# SCH_Wiring-harness-For-Activa_2025-07-03.net
KiCad netlist of a schematic drawn in EasyEDA
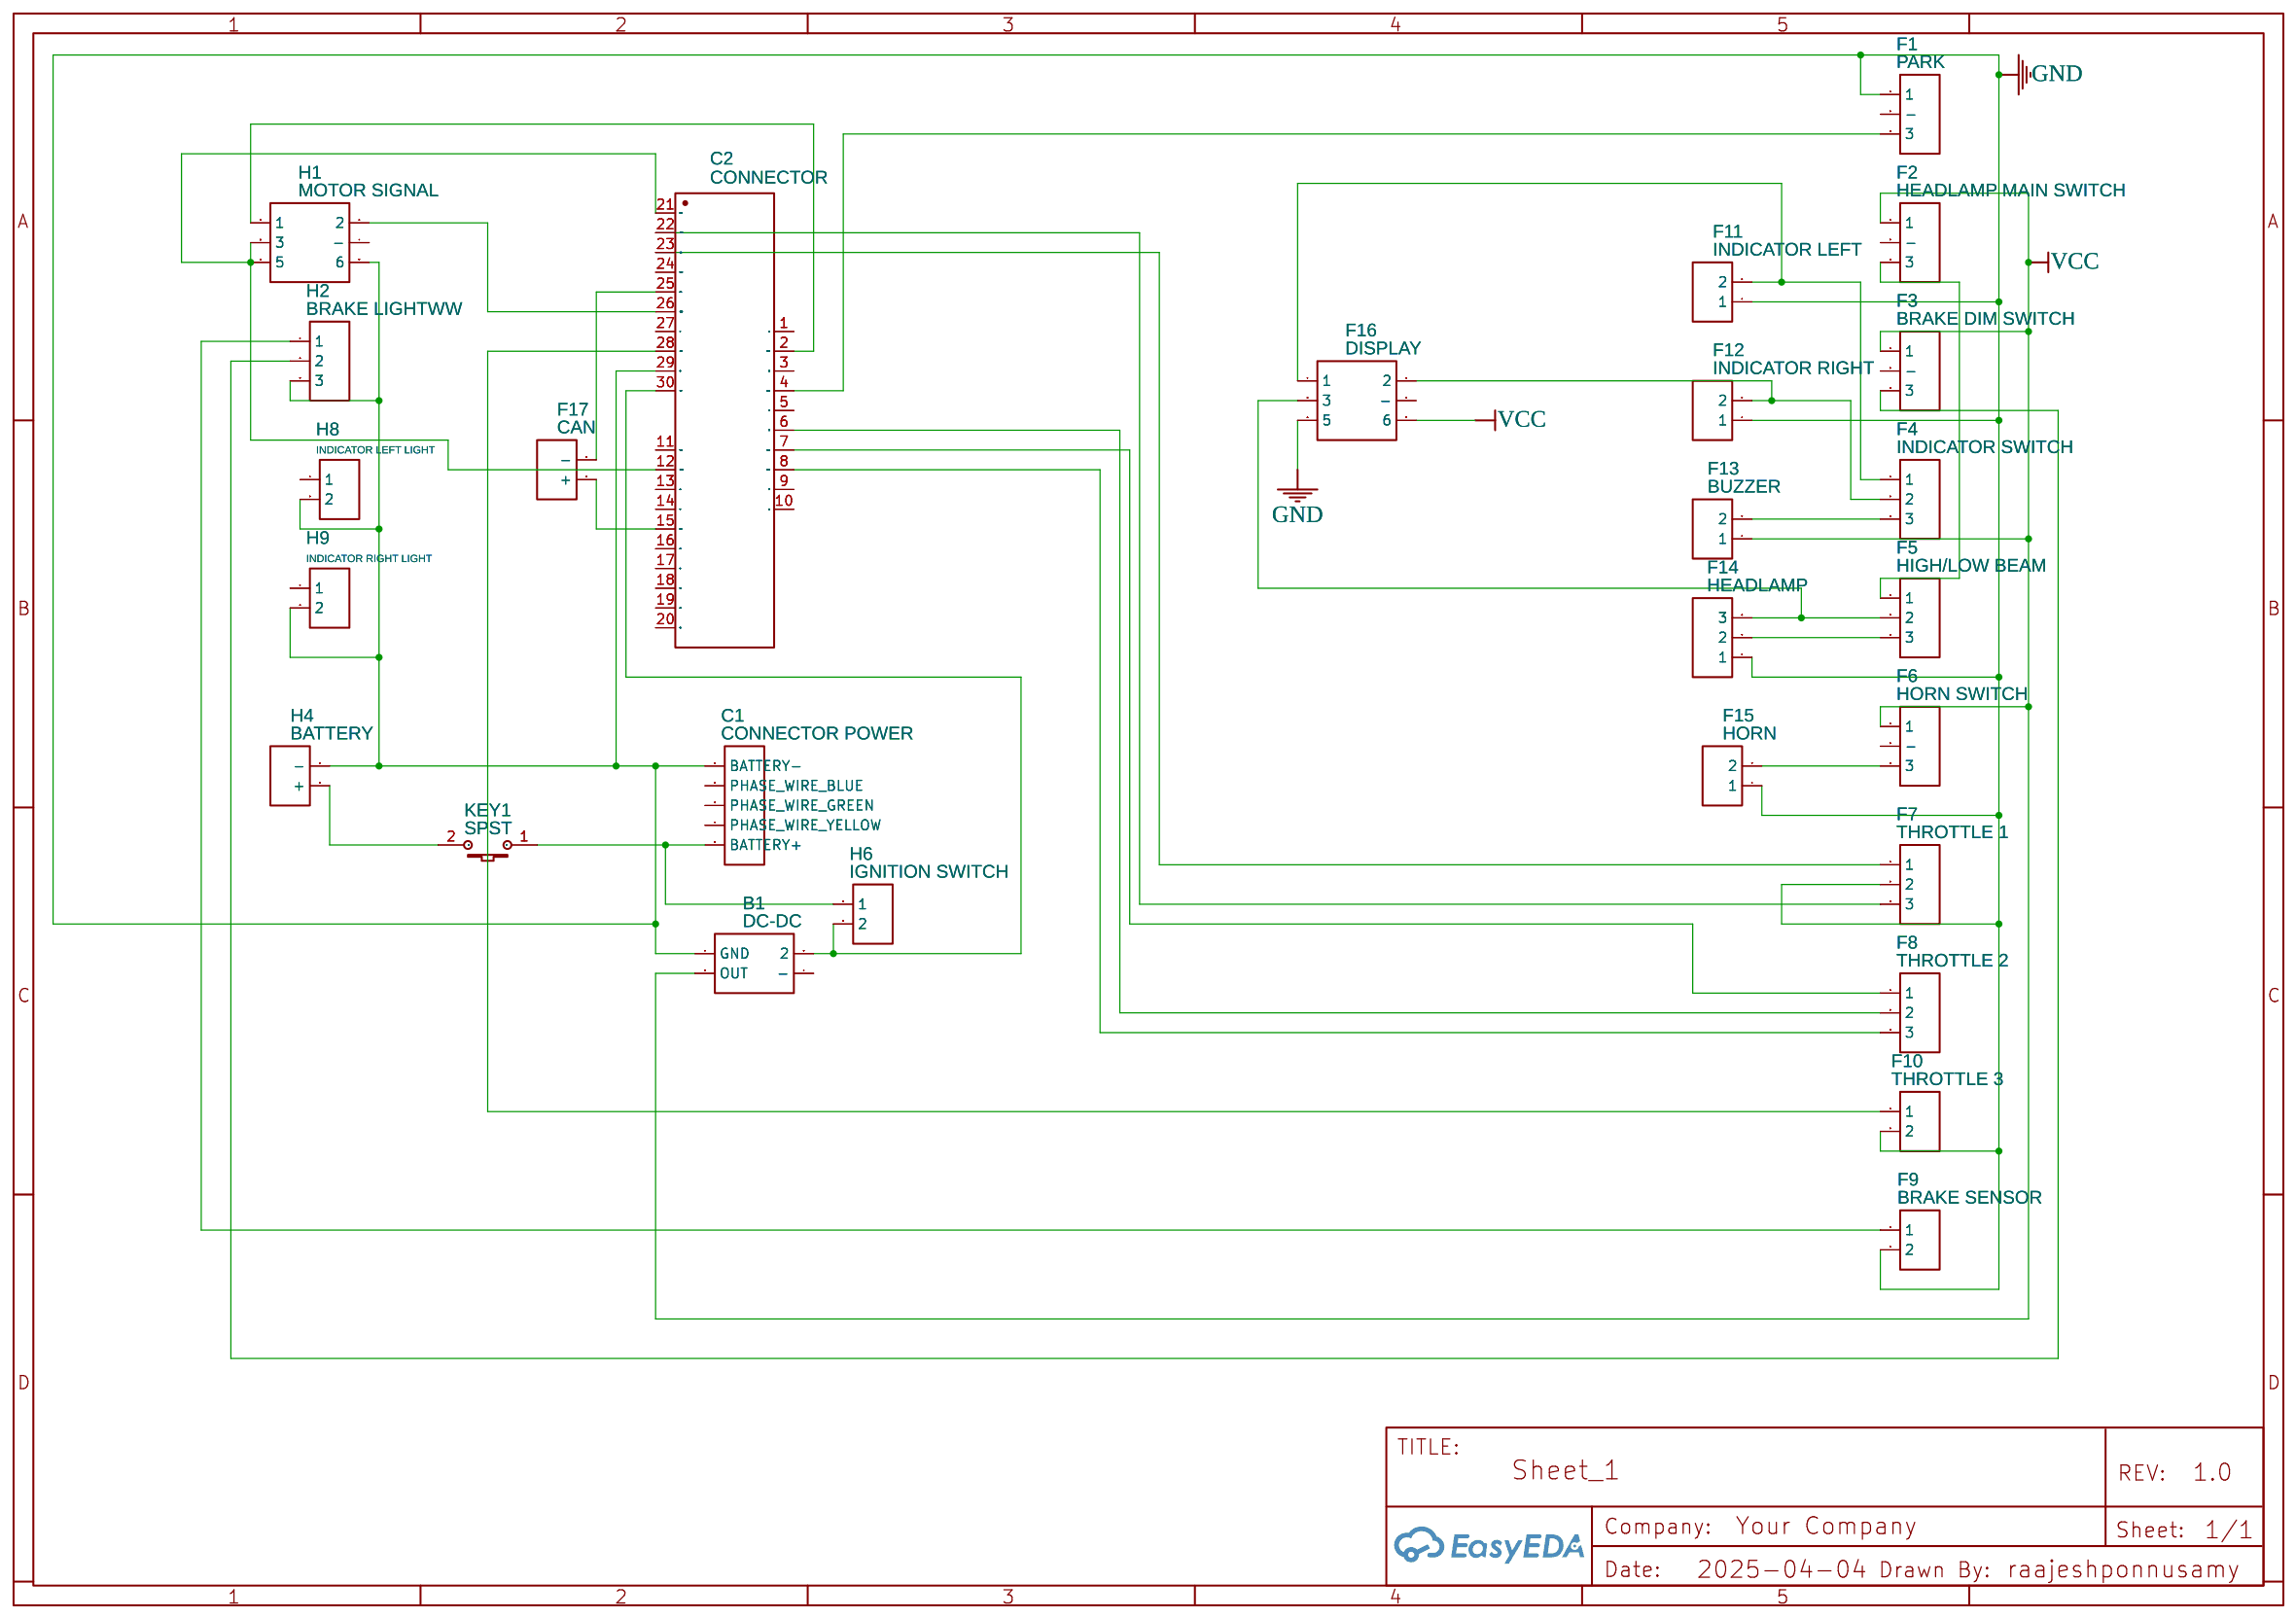
[diagram p0: schematic sheet]

(export (version "E")
  (design (tool "Eeschema 10.0.6"))
  (components
    (comp (ref "B1") (value "DC-DC") (libsource (lib "") (part "HDR-F-2.54_2x2")))
    (comp (ref "C1") (value "CONNECTOR POWER") (libsource (lib "") (part "HDR-F-2.54_1x5")))
    (comp (ref "C2")
      (value "CONNECTOR")
      (fields (field (name "Manufacturer Part") "41612-R(HE 11)"))
      (libsource (lib "") (part "41612-R(HE 11)"))
    )
    (comp (ref "F1") (value "PARK") (libsource (lib "") (part "HDR-F-2.54_1x3")))
    (comp (ref "F2") (value "HEADLAMP MAIN SWITCH") (libsource (lib "") (part "HDR-F-2.54_1x3")))
    (comp (ref "F3") (value "BRAKE DIM SWITCH") (libsource (lib "") (part "HDR-F-2.54_1x3")))
    (comp (ref "F4") (value "INDICATOR SWITCH") (libsource (lib "") (part "HDR-F-2.54_1x3_2")))
    (comp (ref "F5") (value "HIGH/LOW BEAM") (libsource (lib "") (part "HDR-F-2.54_1x3_2")))
    (comp (ref "F6") (value "HORN SWITCH") (libsource (lib "") (part "HDR-F-2.54_1x3")))
    (comp (ref "F7") (value "THROTTLE 1") (libsource (lib "") (part "HDR-F-2.54_1x3_2")))
    (comp (ref "F8") (value "THROTTLE 2") (libsource (lib "") (part "HDR-F-2.54_1x3_2")))
    (comp (ref "F9") (value "BRAKE SENSOR") (libsource (lib "") (part "HDR-F-2.54_1x2_2")))
    (comp (ref "F10") (value "THROTTLE 3") (libsource (lib "") (part "HDR-F-2.54_1x2_2")))
    (comp (ref "F11") (value "INDICATOR LEFT") (libsource (lib "") (part "HDR-F-2.54_1x2_1")))
    (comp (ref "F12") (value "INDICATOR RIGHT") (libsource (lib "") (part "HDR-F-2.54_1x2_1")))
    (comp (ref "F13") (value "BUZZER") (libsource (lib "") (part "HDR-F-2.54_1x2_1")))
    (comp (ref "F14") (value "HEADLAMP") (libsource (lib "") (part "HDR-F-2.54_1x3_3")))
    (comp (ref "F15") (value "HORN") (libsource (lib "") (part "HDR-F-2.54_1x2_1")))
    (comp (ref "F16") (value "DISPLAY") (libsource (lib "") (part "HDR-F-2.54_2x3")))
    (comp (ref "F17") (value "CAN") (libsource (lib "") (part "HDR-F-2.54_1x2_4")))
    (comp (ref "H1") (value "MOTOR SIGNAL") (libsource (lib "") (part "HDR-F-2.54_2x3_1")))
    (comp (ref "H2") (value "BRAKE LIGHTWW") (libsource (lib "") (part "HDR-F-2.54_1x3_1")))
    (comp (ref "H4") (value "BATTERY") (libsource (lib "") (part "HDR-F-2.54_1x2_3")))
    (comp (ref "H6") (value "IGNITION SWITCH") (libsource (lib "") (part "HDR-F-2.54_1x2")))
    (comp (ref "H8") (value "INDICATOR LEFT LIGHT") (libsource (lib "") (part "HDR-F-2.54_1x2")))
    (comp (ref "H9") (value "INDICATOR RIGHT LIGHT") (libsource (lib "") (part "HDR-F-2.54_1x2")))
    (comp (ref "KEY1")
      (value "SPST")
      (fields (field (name "Manufacturer Part") "K2-1107ST-A4SW-06"))
      (libsource (lib "") (part "K2-3.6×6.1_SMD"))
    )
  )
  (nets
    (net (code "1") (name "GND") (class "Default")
      (node (ref "B1") (pin "1") (pinfunction "GND_1") (pintype "unspecified"))
      (node (ref "C1") (pin "1") (pinfunction "BATTERY-_1") (pintype "passive"))
      (node (ref "C2") (pin "29") (pinfunction "GUI_29") (pintype "unspecified"))
      (node (ref "F1") (pin "1") (pinfunction "1_1") (pintype "input"))
      (node (ref "F10") (pin "2") (pinfunction "2_2") (pintype "input"))
      (node (ref "F11") (pin "1") (pinfunction "1_1") (pintype "input"))
      (node (ref "F12") (pin "1") (pinfunction "1_1") (pintype "input"))
      (node (ref "F14") (pin "1") (pinfunction "1_1") (pintype "input"))
      (node (ref "F15") (pin "1") (pinfunction "1_1") (pintype "input"))
      (node (ref "F16") (pin "5") (pinfunction "5_5") (pintype "input"))
      (node (ref "F7") (pin "2") (pinfunction "2_2") (pintype "input"))
      (node (ref "F9") (pin "2") (pinfunction "2_2") (pintype "input"))
      (node (ref "H1") (pin "6") (pinfunction "6_6") (pintype "input"))
      (node (ref "H2") (pin "3") (pinfunction "3_3") (pintype "input"))
      (node (ref "H4") (pin "2") (pinfunction "-_2") (pintype "input"))
      (node (ref "H8") (pin "2") (pinfunction "2_2") (pintype "input"))
      (node (ref "H9") (pin "2") (pinfunction "2_2") (pintype "input"))
    )
    (net (code "2") (name "Net-(C1-BATTERY+)") (class "Default")
      (node (ref "C1") (pin "5") (pinfunction "BATTERY+_5") (pintype "passive"))
      (node (ref "H6") (pin "1") (pinfunction "1_1") (pintype "input"))
      (node (ref "KEY1") (pin "1") (pinfunction "1_1") (pintype "unspecified"))
    )
    (net (code "3") (name "Net-(C2-ANTITHEFT)") (class "Default")
      (node (ref "B1") (pin "2") (pinfunction "2_2") (pintype "unspecified"))
      (node (ref "C2") (pin "30") (pinfunction "ANTITHEFT_30") (pintype "unspecified"))
      (node (ref "H6") (pin "2") (pinfunction "2_2") (pintype "input"))
    )
    (net (code "4") (name "Net-(C2-ANTITHEFT_GND)") (class "Default")
      (node (ref "C2") (pin "7") (pinfunction "ANTITHEFT_GND_7") (pintype "unspecified"))
      (node (ref "F8") (pin "1") (pinfunction "1_1") (pintype "input"))
    )
    (net (code "5") (name "Net-(C2-BRAKE_LOW)") (class "Default")
      (node (ref "C2") (pin "12") (pinfunction "HALL_SENSOR_B_12") (pintype "unspecified"))
      (node (ref "C2") (pin "21") (pinfunction "BRAKE_LOW_21") (pintype "unspecified"))
      (node (ref "H1") (pin "3") (pinfunction "3_3") (pintype "input"))
      (node (ref "H1") (pin "5") (pinfunction "5_5") (pintype "input"))
    )
    (net (code "6") (name "Net-(C2-C6)") (class "Default")
      (node (ref "C2") (pin "6") (pinfunction "C6_6") (pintype "unspecified"))
      (node (ref "F8") (pin "2") (pinfunction "2_2") (pintype "input"))
    )
    (net (code "7") (name "Net-(C2-CAN_HIGH)") (class "Default")
      (node (ref "C2") (pin "15") (pinfunction "CAN_HIGH_15") (pintype "unspecified"))
      (node (ref "F17") (pin "1") (pinfunction "+_1") (pintype "input"))
    )
    (net (code "8") (name "Net-(C2-CAN_LOW)") (class "Default")
      (node (ref "C2") (pin "25") (pinfunction "CAN_LOW_25") (pintype "unspecified"))
      (node (ref "F17") (pin "2") (pinfunction "-_2") (pintype "input"))
    )
    (net (code "9") (name "Net-(C2-HALL_SENSOR_5V)") (class "Default")
      (node (ref "C2") (pin "4") (pinfunction "HALL_SENSOR_5V_4") (pintype "unspecified"))
      (node (ref "F1") (pin "3") (pinfunction "3_3") (pintype "input"))
    )
    (net (code "10") (name "Net-(C2-HALL_SENSOR_C)") (class "Default")
      (node (ref "C2") (pin "22") (pinfunction "HALL_SENSOR_C_22") (pintype "unspecified"))
      (node (ref "F7") (pin "3") (pinfunction "3_3") (pintype "input"))
    )
    (net (code "11") (name "Net-(C2-LOW_GEAR_INPUT)") (class "Default")
      (node (ref "C2") (pin "2") (pinfunction "LOW_GEAR_INPUT_2") (pintype "unspecified"))
      (node (ref "H1") (pin "1") (pinfunction "1_1") (pintype "input"))
    )
    (net (code "12") (name "Net-(C2-REVERSE_INPUT)") (class "Default")
      (node (ref "C2") (pin "8") (pinfunction "REVERSE_INPUT_8") (pintype "unspecified"))
      (node (ref "F8") (pin "3") (pinfunction "3_3") (pintype "input"))
    )
    (net (code "13") (name "Net-(C2-RX{slash}485B)") (class "Default")
      (node (ref "C2") (pin "23") (pinfunction "RX/485B_23") (pintype "unspecified"))
      (node (ref "F7") (pin "1") (pinfunction "1_1") (pintype "input"))
    )
    (net (code "14") (name "Net-(C2-THROTTLE_5V)") (class "Default")
      (node (ref "C2") (pin "28") (pinfunction "THROTTLE_5V_28") (pintype "unspecified"))
      (node (ref "F10") (pin "1") (pinfunction "1_1") (pintype "input"))
    )
    (net (code "15") (name "Net-(C2-THROTTLE_GND)") (class "Default")
      (node (ref "C2") (pin "26") (pinfunction "THROTTLE_GND_26") (pintype "unspecified"))
      (node (ref "H1") (pin "2") (pinfunction "2_2") (pintype "input"))
    )
    (net (code "16") (name "Net-(F2-Pad3)") (class "Default")
      (node (ref "F2") (pin "3") (pinfunction "3_3") (pintype "input"))
      (node (ref "F5") (pin "1") (pinfunction "1_1") (pintype "input"))
    )
    (net (code "17") (name "Net-(F3-Pad3)") (class "Default")
      (node (ref "F3") (pin "3") (pinfunction "3_3") (pintype "input"))
      (node (ref "H2") (pin "2") (pinfunction "2_2") (pintype "input"))
    )
    (net (code "18") (name "Net-(F9-Pad1)") (class "Default")
      (node (ref "F9") (pin "1") (pinfunction "1_1") (pintype "input"))
      (node (ref "H2") (pin "1") (pinfunction "1_1") (pintype "input"))
    )
    (net (code "19") (name "Net-(F11-Pad2)") (class "Default")
      (node (ref "F11") (pin "2") (pinfunction "2_2") (pintype "input"))
      (node (ref "F16") (pin "1") (pinfunction "1_1") (pintype "input"))
      (node (ref "F4") (pin "1") (pinfunction "1_1") (pintype "input"))
    )
    (net (code "20") (name "Net-(F12-Pad2)") (class "Default")
      (node (ref "F12") (pin "2") (pinfunction "2_2") (pintype "input"))
      (node (ref "F16") (pin "2") (pinfunction "2_2") (pintype "input"))
      (node (ref "F4") (pin "2") (pinfunction "2_2") (pintype "input"))
    )
    (net (code "21") (name "Net-(F13-Pad2)") (class "Default")
      (node (ref "F13") (pin "2") (pinfunction "2_2") (pintype "input"))
      (node (ref "F4") (pin "3") (pinfunction "3_3") (pintype "input"))
    )
    (net (code "22") (name "Net-(F14-Pad2)") (class "Default")
      (node (ref "F14") (pin "2") (pinfunction "2_2") (pintype "input"))
      (node (ref "F5") (pin "3") (pinfunction "3_3") (pintype "input"))
    )
    (net (code "23") (name "Net-(F14-Pad3)") (class "Default")
      (node (ref "F14") (pin "3") (pinfunction "3_3") (pintype "input"))
      (node (ref "F16") (pin "3") (pinfunction "3_3") (pintype "input"))
      (node (ref "F5") (pin "2") (pinfunction "2_2") (pintype "input"))
    )
    (net (code "24") (name "Net-(F15-Pad2)") (class "Default")
      (node (ref "F15") (pin "2") (pinfunction "2_2") (pintype "input"))
      (node (ref "F6") (pin "3") (pinfunction "3_3") (pintype "input"))
    )
    (net (code "25") (name "Net-(H4-+)") (class "Default")
      (node (ref "H4") (pin "1") (pinfunction "+_1") (pintype "input"))
      (node (ref "KEY1") (pin "2") (pinfunction "2_2") (pintype "unspecified"))
    )
    (net (code "26") (name "VCC") (class "Default")
      (node (ref "B1") (pin "3") (pinfunction "OUT_3") (pintype "unspecified"))
      (node (ref "F13") (pin "1") (pinfunction "1_1") (pintype "input"))
      (node (ref "F16") (pin "6") (pinfunction "6_6") (pintype "input"))
      (node (ref "F2") (pin "1") (pinfunction "1_1") (pintype "input"))
      (node (ref "F3") (pin "1") (pinfunction "1_1") (pintype "input"))
      (node (ref "F6") (pin "1") (pinfunction "1_1") (pintype "input"))
    )
    (net (code "27") (name "unconnected-(B1---Pad4)") (class "Default")
      (node (ref "B1") (pin "4") (pinfunction "-_4") (pintype "unspecified"))
    )
    (net (code "28") (name "unconnected-(C1-PHASE_WIRE_BLUE-Pad2)") (class "Default")
      (node (ref "C1") (pin "2") (pinfunction "PHASE_WIRE_BLUE_2") (pintype "unspecified"))
    )
    (net (code "29") (name "unconnected-(C1-PHASE_WIRE_GREEN-Pad3)") (class "Default")
      (node (ref "C1") (pin "3") (pinfunction "PHASE_WIRE_GREEN_3") (pintype "unspecified"))
    )
    (net (code "30") (name "unconnected-(C1-PHASE_WIRE_YELLOW-Pad4)") (class "Default")
      (node (ref "C1") (pin "4") (pinfunction "PHASE_WIRE_YELLOW_4") (pintype "unspecified"))
    )
    (net (code "31") (name "unconnected-(C2-A7-Pad27)") (class "Default")
      (node (ref "C2") (pin "27") (pinfunction "A7_27") (pintype "unspecified"))
    )
    (net (code "32") (name "unconnected-(C2-B3-Pad13)") (class "Default")
      (node (ref "C2") (pin "13") (pinfunction "B3_13") (pintype "unspecified"))
    )
    (net (code "33") (name "unconnected-(C2-B4-Pad14)") (class "Default")
      (node (ref "C2") (pin "14") (pinfunction "B4_14") (pintype "unspecified"))
    )
    (net (code "34") (name "unconnected-(C2-B6-Pad16)") (class "Default")
      (node (ref "C2") (pin "16") (pinfunction "B6_16") (pintype "unspecified"))
    )
    (net (code "35") (name "unconnected-(C2-B7-Pad17)") (class "Default")
      (node (ref "C2") (pin "17") (pinfunction "B7_17") (pintype "unspecified"))
    )
    (net (code "36") (name "unconnected-(C2-B8-Pad18)") (class "Default")
      (node (ref "C2") (pin "18") (pinfunction "B8_18") (pintype "unspecified"))
    )
    (net (code "37") (name "unconnected-(C2-B9-Pad19)") (class "Default")
      (node (ref "C2") (pin "19") (pinfunction "B9_19") (pintype "unspecified"))
    )
    (net (code "38") (name "unconnected-(C2-B10-Pad20)") (class "Default")
      (node (ref "C2") (pin "20") (pinfunction "B10_20") (pintype "unspecified"))
    )
    (net (code "39") (name "unconnected-(C2-BRAKE_HIGH-Pad11)") (class "Default")
      (node (ref "C2") (pin "11") (pinfunction "BRAKE_HIGH_11") (pintype "unspecified"))
    )
    (net (code "40") (name "unconnected-(C2-C1-Pad1)") (class "Default")
      (node (ref "C2") (pin "1") (pinfunction "C1_1") (pintype "unspecified"))
    )
    (net (code "41") (name "unconnected-(C2-C3-Pad3)") (class "Default")
      (node (ref "C2") (pin "3") (pinfunction "C3_3") (pintype "unspecified"))
    )
    (net (code "42") (name "unconnected-(C2-C5-Pad5)") (class "Default")
      (node (ref "C2") (pin "5") (pinfunction "C5_5") (pintype "unspecified"))
    )
    (net (code "43") (name "unconnected-(C2-C9-Pad9)") (class "Default")
      (node (ref "C2") (pin "9") (pinfunction "C9_9") (pintype "unspecified"))
    )
    (net (code "44") (name "unconnected-(C2-C10-Pad10)") (class "Default")
      (node (ref "C2") (pin "10") (pinfunction "C10_10") (pintype "unspecified"))
    )
    (net (code "45") (name "unconnected-(C2-RESERVE_INPUT-Pad24)") (class "Default")
      (node (ref "C2") (pin "24") (pinfunction "RESERVE_INPUT_24") (pintype "unspecified"))
    )
    (net (code "46") (name "unconnected-(F1---Pad2)") (class "Default")
      (node (ref "F1") (pin "2") (pinfunction "-_2") (pintype "input"))
    )
    (net (code "47") (name "unconnected-(F2---Pad2)") (class "Default")
      (node (ref "F2") (pin "2") (pinfunction "-_2") (pintype "input"))
    )
    (net (code "48") (name "unconnected-(F3---Pad2)") (class "Default")
      (node (ref "F3") (pin "2") (pinfunction "-_2") (pintype "input"))
    )
    (net (code "49") (name "unconnected-(F6---Pad2)") (class "Default")
      (node (ref "F6") (pin "2") (pinfunction "-_2") (pintype "input"))
    )
    (net (code "50") (name "unconnected-(F16---Pad4)") (class "Default")
      (node (ref "F16") (pin "4") (pinfunction "-_4") (pintype "input"))
    )
    (net (code "51") (name "unconnected-(H1---Pad4)") (class "Default")
      (node (ref "H1") (pin "4") (pinfunction "-_4") (pintype "input"))
    )
    (net (code "52") (name "unconnected-(H8-Pad1)") (class "Default")
      (node (ref "H8") (pin "1") (pinfunction "1_1") (pintype "input"))
    )
    (net (code "53") (name "unconnected-(H9-Pad1)") (class "Default")
      (node (ref "H9") (pin "1") (pinfunction "1_1") (pintype "input"))
    )
  )
)
